# headstage.net
KiCad netlist of a schematic drawn in EAGLE
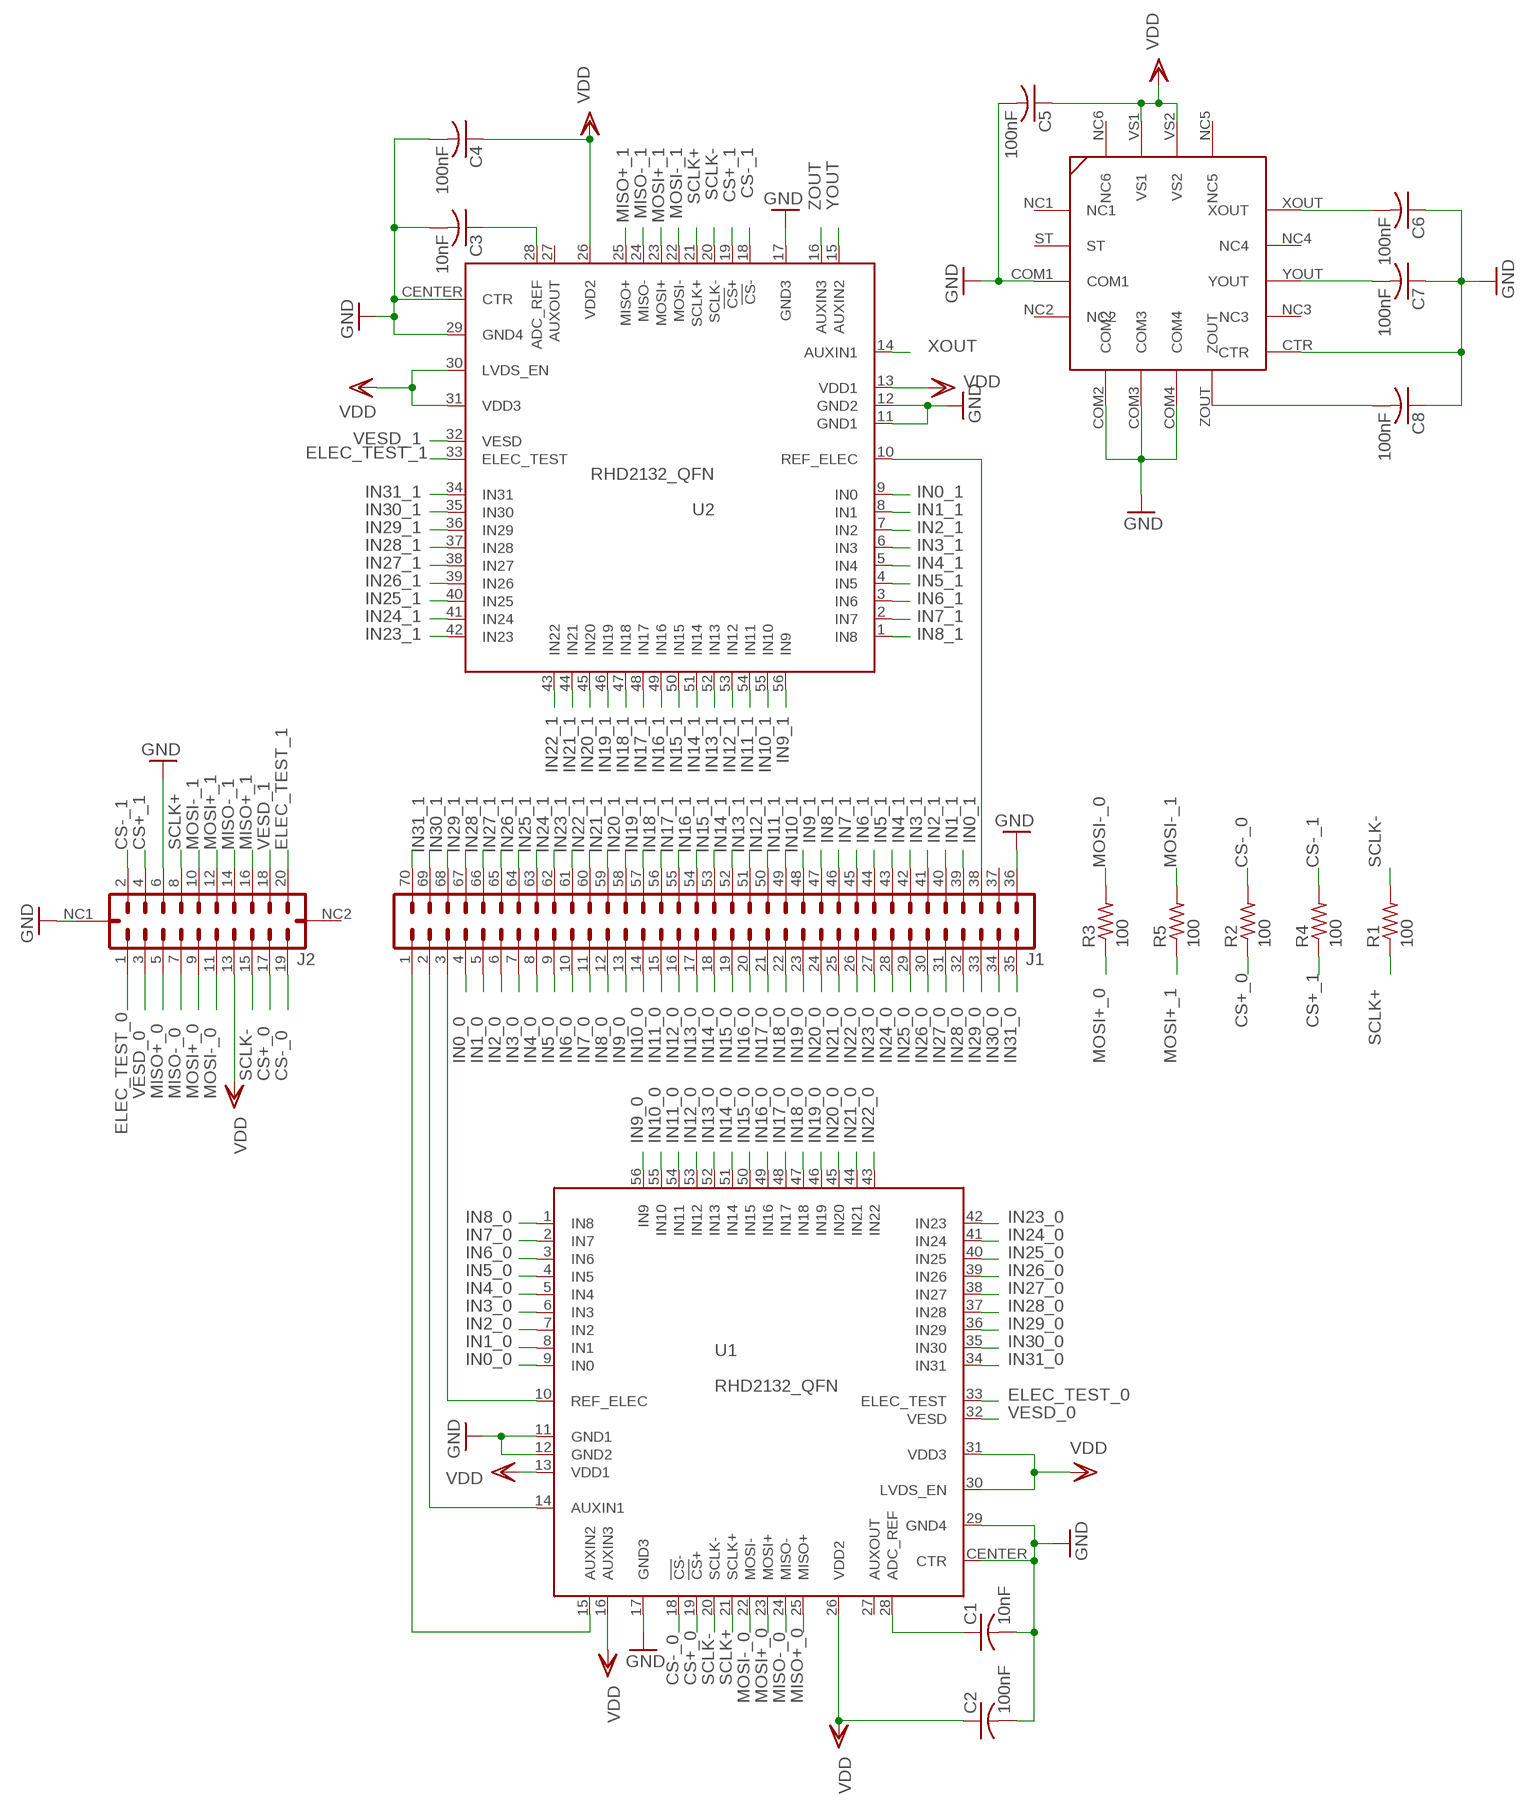
[diagram p0: schematic, sheet 1]

(export (version "E")
  (design (tool "Eeschema 10.0.6"))
  (components
    (comp (ref "C1")
      (value "10nF")
      (footprint "eagle-import:C0402K")
      (libsource (lib "eagle-import") (part "C-USC0402K"))
    )
    (comp (ref "C2")
      (value "100nF")
      (footprint "eagle-import:C0402K")
      (libsource (lib "eagle-import") (part "C-USC0402K"))
    )
    (comp (ref "C3")
      (value "10nF")
      (footprint "eagle-import:C0402K")
      (libsource (lib "eagle-import") (part "C-USC0402K"))
    )
    (comp (ref "C4")
      (value "100nF")
      (footprint "eagle-import:C0402K")
      (libsource (lib "eagle-import") (part "C-USC0402K"))
    )
    (comp (ref "C5")
      (value "100nF")
      (footprint "eagle-import:C0402K")
      (libsource (lib "eagle-import") (part "C-USC0402K"))
    )
    (comp (ref "C6")
      (value "100nF")
      (footprint "eagle-import:C0402K")
      (libsource (lib "eagle-import") (part "C-USC0402K"))
    )
    (comp (ref "C7")
      (value "100nF")
      (footprint "eagle-import:C0402K")
      (libsource (lib "eagle-import") (part "C-USC0402K"))
    )
    (comp (ref "C8")
      (value "100nF")
      (footprint "eagle-import:C0402K")
      (libsource (lib "eagle-import") (part "C-USC0402K"))
    )
    (comp (ref "J1")
      (value "HIROSE_DF40C-70DS-0.4V(51)")
      (footprint "eagle-import:HIROSE_DF40C-70DP")
      (libsource (lib "eagle-import") (part "HIROSE_DF40-70DP"))
    )
    (comp (ref "J2")
      (value "MOLEX_501190-2017")
      (footprint "eagle-import:MOLEX_501190-2017")
      (libsource (lib "eagle-import") (part "MOLEX_501190-2017"))
    )
    (comp (ref "R1")
      (value "100")
      (footprint "eagle-import:R0402")
      (libsource (lib "eagle-import") (part "R-US_R0402"))
    )
    (comp (ref "R2")
      (value "100")
      (footprint "eagle-import:R0402")
      (libsource (lib "eagle-import") (part "R-US_R0402"))
    )
    (comp (ref "R3")
      (value "100")
      (footprint "eagle-import:R0402")
      (libsource (lib "eagle-import") (part "R-US_R0402"))
    )
    (comp (ref "R4")
      (value "100")
      (footprint "eagle-import:R0402")
      (libsource (lib "eagle-import") (part "R-US_R0402"))
    )
    (comp (ref "R5")
      (value "100")
      (footprint "eagle-import:R0402")
      (libsource (lib "eagle-import") (part "R-US_R0402"))
    )
    (comp (ref "U1")
      (value "RHD2132_QFN")
      (footprint "eagle-import:QFN56_8_X_8_LARGE")
      (libsource (lib "eagle-import") (part "RHD2132_QFN"))
    )
    (comp (ref "U2")
      (value "RHD2132_QFN")
      (footprint "eagle-import:QFN56_8_X_8_LARGE")
      (libsource (lib "eagle-import") (part "RHD2132_QFN"))
    )
    (comp (ref "U3")
      (value "ADXL335")
      (footprint "eagle-import:ADXL335")
      (libsource (lib "eagle-import") (part "ADXL335"))
    )
  )
  (nets
    (net (code "1") (name "/CS+_0") (class "Default")
      (node (ref "J2") (pin "17") (pinfunction "17_17") (pintype "passive"))
      (node (ref "R2") (pin "1") (pinfunction "1_1") (pintype "passive"))
      (node (ref "U1") (pin "19") (pinfunction "~{CS}+_19") (pintype "input"))
    )
    (net (code "2") (name "/CS+_1") (class "Default")
      (node (ref "J2") (pin "4") (pinfunction "4_4") (pintype "passive"))
      (node (ref "R4") (pin "1") (pinfunction "1_1") (pintype "passive"))
      (node (ref "U2") (pin "19") (pinfunction "~{CS}+_19") (pintype "input"))
    )
    (net (code "3") (name "/CS-_0") (class "Default")
      (node (ref "J2") (pin "19") (pinfunction "19_19") (pintype "passive"))
      (node (ref "R2") (pin "2") (pinfunction "2_2") (pintype "passive"))
      (node (ref "U1") (pin "18") (pinfunction "~{CS}-_18") (pintype "input"))
    )
    (net (code "4") (name "/CS-_1") (class "Default")
      (node (ref "J2") (pin "2") (pinfunction "2_2") (pintype "passive"))
      (node (ref "R4") (pin "2") (pinfunction "2_2") (pintype "passive"))
      (node (ref "U2") (pin "18") (pinfunction "~{CS}-_18") (pintype "input"))
    )
    (net (code "5") (name "/ELEC_TEST_0") (class "Default")
      (node (ref "J2") (pin "1") (pinfunction "1_1") (pintype "passive"))
      (node (ref "U1") (pin "33") (pinfunction "ELEC_TEST_33") (pintype "input"))
    )
    (net (code "6") (name "/ELEC_TEST_1") (class "Default")
      (node (ref "J2") (pin "20") (pinfunction "20_20") (pintype "passive"))
      (node (ref "U2") (pin "33") (pinfunction "ELEC_TEST_33") (pintype "input"))
    )
    (net (code "7") (name "/IN0_0") (class "Default")
      (node (ref "J1") (pin "4") (pinfunction "4_4") (pintype "passive"))
      (node (ref "U1") (pin "9") (pinfunction "IN0_9") (pintype "input"))
    )
    (net (code "8") (name "/IN0_1") (class "Default")
      (node (ref "J1") (pin "39") (pinfunction "39_39") (pintype "passive"))
      (node (ref "U2") (pin "9") (pinfunction "IN0_9") (pintype "input"))
    )
    (net (code "9") (name "/IN1_0") (class "Default")
      (node (ref "J1") (pin "5") (pinfunction "5_5") (pintype "passive"))
      (node (ref "U1") (pin "8") (pinfunction "IN1_8") (pintype "input"))
    )
    (net (code "10") (name "/IN1_1") (class "Default")
      (node (ref "J1") (pin "40") (pinfunction "40_40") (pintype "passive"))
      (node (ref "U2") (pin "8") (pinfunction "IN1_8") (pintype "input"))
    )
    (net (code "11") (name "/IN2_0") (class "Default")
      (node (ref "J1") (pin "6") (pinfunction "6_6") (pintype "passive"))
      (node (ref "U1") (pin "7") (pinfunction "IN2_7") (pintype "input"))
    )
    (net (code "12") (name "/IN2_1") (class "Default")
      (node (ref "J1") (pin "41") (pinfunction "41_41") (pintype "passive"))
      (node (ref "U2") (pin "7") (pinfunction "IN2_7") (pintype "input"))
    )
    (net (code "13") (name "/IN3_0") (class "Default")
      (node (ref "J1") (pin "7") (pinfunction "7_7") (pintype "passive"))
      (node (ref "U1") (pin "6") (pinfunction "IN3_6") (pintype "input"))
    )
    (net (code "14") (name "/IN3_1") (class "Default")
      (node (ref "J1") (pin "42") (pinfunction "42_42") (pintype "passive"))
      (node (ref "U2") (pin "6") (pinfunction "IN3_6") (pintype "input"))
    )
    (net (code "15") (name "/IN4_0") (class "Default")
      (node (ref "J1") (pin "8") (pinfunction "8_8") (pintype "passive"))
      (node (ref "U1") (pin "5") (pinfunction "IN4_5") (pintype "input"))
    )
    (net (code "16") (name "/IN4_1") (class "Default")
      (node (ref "J1") (pin "43") (pinfunction "43_43") (pintype "passive"))
      (node (ref "U2") (pin "5") (pinfunction "IN4_5") (pintype "input"))
    )
    (net (code "17") (name "/IN5_0") (class "Default")
      (node (ref "J1") (pin "9") (pinfunction "9_9") (pintype "passive"))
      (node (ref "U1") (pin "4") (pinfunction "IN5_4") (pintype "input"))
    )
    (net (code "18") (name "/IN5_1") (class "Default")
      (node (ref "J1") (pin "44") (pinfunction "44_44") (pintype "passive"))
      (node (ref "U2") (pin "4") (pinfunction "IN5_4") (pintype "input"))
    )
    (net (code "19") (name "/IN6_0") (class "Default")
      (node (ref "J1") (pin "10") (pinfunction "10_10") (pintype "passive"))
      (node (ref "U1") (pin "3") (pinfunction "IN6_3") (pintype "input"))
    )
    (net (code "20") (name "/IN6_1") (class "Default")
      (node (ref "J1") (pin "45") (pinfunction "45_45") (pintype "passive"))
      (node (ref "U2") (pin "3") (pinfunction "IN6_3") (pintype "input"))
    )
    (net (code "21") (name "/IN7_0") (class "Default")
      (node (ref "J1") (pin "11") (pinfunction "11_11") (pintype "passive"))
      (node (ref "U1") (pin "2") (pinfunction "IN7_2") (pintype "input"))
    )
    (net (code "22") (name "/IN7_1") (class "Default")
      (node (ref "J1") (pin "46") (pinfunction "46_46") (pintype "passive"))
      (node (ref "U2") (pin "2") (pinfunction "IN7_2") (pintype "input"))
    )
    (net (code "23") (name "/IN8_0") (class "Default")
      (node (ref "J1") (pin "12") (pinfunction "12_12") (pintype "passive"))
      (node (ref "U1") (pin "1") (pinfunction "IN8_1") (pintype "input"))
    )
    (net (code "24") (name "/IN8_1") (class "Default")
      (node (ref "J1") (pin "47") (pinfunction "47_47") (pintype "passive"))
      (node (ref "U2") (pin "1") (pinfunction "IN8_1") (pintype "input"))
    )
    (net (code "25") (name "/IN9_0") (class "Default")
      (node (ref "J1") (pin "13") (pinfunction "13_13") (pintype "passive"))
      (node (ref "U1") (pin "56") (pinfunction "IN9_56") (pintype "input"))
    )
    (net (code "26") (name "/IN9_1") (class "Default")
      (node (ref "J1") (pin "48") (pinfunction "48_48") (pintype "passive"))
      (node (ref "U2") (pin "56") (pinfunction "IN9_56") (pintype "input"))
    )
    (net (code "27") (name "/IN10_0") (class "Default")
      (node (ref "J1") (pin "14") (pinfunction "14_14") (pintype "passive"))
      (node (ref "U1") (pin "55") (pinfunction "IN10_55") (pintype "input"))
    )
    (net (code "28") (name "/IN10_1") (class "Default")
      (node (ref "J1") (pin "49") (pinfunction "49_49") (pintype "passive"))
      (node (ref "U2") (pin "55") (pinfunction "IN10_55") (pintype "input"))
    )
    (net (code "29") (name "/IN11_0") (class "Default")
      (node (ref "J1") (pin "15") (pinfunction "15_15") (pintype "passive"))
      (node (ref "U1") (pin "54") (pinfunction "IN11_54") (pintype "input"))
    )
    (net (code "30") (name "/IN11_1") (class "Default")
      (node (ref "J1") (pin "50") (pinfunction "50_50") (pintype "passive"))
      (node (ref "U2") (pin "54") (pinfunction "IN11_54") (pintype "input"))
    )
    (net (code "31") (name "/IN12_0") (class "Default")
      (node (ref "J1") (pin "16") (pinfunction "16_16") (pintype "passive"))
      (node (ref "U1") (pin "53") (pinfunction "IN12_53") (pintype "input"))
    )
    (net (code "32") (name "/IN12_1") (class "Default")
      (node (ref "J1") (pin "51") (pinfunction "51_51") (pintype "passive"))
      (node (ref "U2") (pin "53") (pinfunction "IN12_53") (pintype "input"))
    )
    (net (code "33") (name "/IN13_0") (class "Default")
      (node (ref "J1") (pin "17") (pinfunction "17_17") (pintype "passive"))
      (node (ref "U1") (pin "52") (pinfunction "IN13_52") (pintype "input"))
    )
    (net (code "34") (name "/IN13_1") (class "Default")
      (node (ref "J1") (pin "52") (pinfunction "52_52") (pintype "passive"))
      (node (ref "U2") (pin "52") (pinfunction "IN13_52") (pintype "input"))
    )
    (net (code "35") (name "/IN14_0") (class "Default")
      (node (ref "J1") (pin "18") (pinfunction "18_18") (pintype "passive"))
      (node (ref "U1") (pin "51") (pinfunction "IN14_51") (pintype "input"))
    )
    (net (code "36") (name "/IN14_1") (class "Default")
      (node (ref "J1") (pin "53") (pinfunction "53_53") (pintype "passive"))
      (node (ref "U2") (pin "51") (pinfunction "IN14_51") (pintype "input"))
    )
    (net (code "37") (name "/IN15_0") (class "Default")
      (node (ref "J1") (pin "19") (pinfunction "19_19") (pintype "passive"))
      (node (ref "U1") (pin "50") (pinfunction "IN15_50") (pintype "input"))
    )
    (net (code "38") (name "/IN15_1") (class "Default")
      (node (ref "J1") (pin "54") (pinfunction "54_54") (pintype "passive"))
      (node (ref "U2") (pin "50") (pinfunction "IN15_50") (pintype "input"))
    )
    (net (code "39") (name "/IN16_0") (class "Default")
      (node (ref "J1") (pin "20") (pinfunction "20_20") (pintype "passive"))
      (node (ref "U1") (pin "49") (pinfunction "IN16_49") (pintype "input"))
    )
    (net (code "40") (name "/IN16_1") (class "Default")
      (node (ref "J1") (pin "55") (pinfunction "55_55") (pintype "passive"))
      (node (ref "U2") (pin "49") (pinfunction "IN16_49") (pintype "input"))
    )
    (net (code "41") (name "/IN17_0") (class "Default")
      (node (ref "J1") (pin "21") (pinfunction "21_21") (pintype "passive"))
      (node (ref "U1") (pin "48") (pinfunction "IN17_48") (pintype "input"))
    )
    (net (code "42") (name "/IN17_1") (class "Default")
      (node (ref "J1") (pin "56") (pinfunction "56_56") (pintype "passive"))
      (node (ref "U2") (pin "48") (pinfunction "IN17_48") (pintype "input"))
    )
    (net (code "43") (name "/IN18_0") (class "Default")
      (node (ref "J1") (pin "22") (pinfunction "22_22") (pintype "passive"))
      (node (ref "U1") (pin "47") (pinfunction "IN18_47") (pintype "input"))
    )
    (net (code "44") (name "/IN18_1") (class "Default")
      (node (ref "J1") (pin "57") (pinfunction "57_57") (pintype "passive"))
      (node (ref "U2") (pin "47") (pinfunction "IN18_47") (pintype "input"))
    )
    (net (code "45") (name "/IN19_0") (class "Default")
      (node (ref "J1") (pin "23") (pinfunction "23_23") (pintype "passive"))
      (node (ref "U1") (pin "46") (pinfunction "IN19_46") (pintype "input"))
    )
    (net (code "46") (name "/IN19_1") (class "Default")
      (node (ref "J1") (pin "58") (pinfunction "58_58") (pintype "passive"))
      (node (ref "U2") (pin "46") (pinfunction "IN19_46") (pintype "input"))
    )
    (net (code "47") (name "/IN20_0") (class "Default")
      (node (ref "J1") (pin "24") (pinfunction "24_24") (pintype "passive"))
      (node (ref "U1") (pin "45") (pinfunction "IN20_45") (pintype "input"))
    )
    (net (code "48") (name "/IN20_1") (class "Default")
      (node (ref "J1") (pin "59") (pinfunction "59_59") (pintype "passive"))
      (node (ref "U2") (pin "45") (pinfunction "IN20_45") (pintype "input"))
    )
    (net (code "49") (name "/IN21_0") (class "Default")
      (node (ref "J1") (pin "25") (pinfunction "25_25") (pintype "passive"))
      (node (ref "U1") (pin "44") (pinfunction "IN21_44") (pintype "input"))
    )
    (net (code "50") (name "/IN21_1") (class "Default")
      (node (ref "J1") (pin "60") (pinfunction "60_60") (pintype "passive"))
      (node (ref "U2") (pin "44") (pinfunction "IN21_44") (pintype "input"))
    )
    (net (code "51") (name "/IN22_0") (class "Default")
      (node (ref "J1") (pin "26") (pinfunction "26_26") (pintype "passive"))
      (node (ref "U1") (pin "43") (pinfunction "IN22_43") (pintype "input"))
    )
    (net (code "52") (name "/IN22_1") (class "Default")
      (node (ref "J1") (pin "61") (pinfunction "61_61") (pintype "passive"))
      (node (ref "U2") (pin "43") (pinfunction "IN22_43") (pintype "input"))
    )
    (net (code "53") (name "/IN23_0") (class "Default")
      (node (ref "J1") (pin "27") (pinfunction "27_27") (pintype "passive"))
      (node (ref "U1") (pin "42") (pinfunction "IN23_42") (pintype "input"))
    )
    (net (code "54") (name "/IN23_1") (class "Default")
      (node (ref "J1") (pin "62") (pinfunction "62_62") (pintype "passive"))
      (node (ref "U2") (pin "42") (pinfunction "IN23_42") (pintype "input"))
    )
    (net (code "55") (name "/IN24_0") (class "Default")
      (node (ref "J1") (pin "28") (pinfunction "28_28") (pintype "passive"))
      (node (ref "U1") (pin "41") (pinfunction "IN24_41") (pintype "input"))
    )
    (net (code "56") (name "/IN24_1") (class "Default")
      (node (ref "J1") (pin "63") (pinfunction "63_63") (pintype "passive"))
      (node (ref "U2") (pin "41") (pinfunction "IN24_41") (pintype "input"))
    )
    (net (code "57") (name "/IN25_0") (class "Default")
      (node (ref "J1") (pin "29") (pinfunction "29_29") (pintype "passive"))
      (node (ref "U1") (pin "40") (pinfunction "IN25_40") (pintype "input"))
    )
    (net (code "58") (name "/IN25_1") (class "Default")
      (node (ref "J1") (pin "64") (pinfunction "64_64") (pintype "passive"))
      (node (ref "U2") (pin "40") (pinfunction "IN25_40") (pintype "input"))
    )
    (net (code "59") (name "/IN26_0") (class "Default")
      (node (ref "J1") (pin "30") (pinfunction "30_30") (pintype "passive"))
      (node (ref "U1") (pin "39") (pinfunction "IN26_39") (pintype "input"))
    )
    (net (code "60") (name "/IN26_1") (class "Default")
      (node (ref "J1") (pin "65") (pinfunction "65_65") (pintype "passive"))
      (node (ref "U2") (pin "39") (pinfunction "IN26_39") (pintype "input"))
    )
    (net (code "61") (name "/IN27_0") (class "Default")
      (node (ref "J1") (pin "31") (pinfunction "31_31") (pintype "passive"))
      (node (ref "U1") (pin "38") (pinfunction "IN27_38") (pintype "input"))
    )
    (net (code "62") (name "/IN27_1") (class "Default")
      (node (ref "J1") (pin "66") (pinfunction "66_66") (pintype "passive"))
      (node (ref "U2") (pin "38") (pinfunction "IN27_38") (pintype "input"))
    )
    (net (code "63") (name "/IN28_0") (class "Default")
      (node (ref "J1") (pin "32") (pinfunction "32_32") (pintype "passive"))
      (node (ref "U1") (pin "37") (pinfunction "IN28_37") (pintype "input"))
    )
    (net (code "64") (name "/IN28_1") (class "Default")
      (node (ref "J1") (pin "67") (pinfunction "67_67") (pintype "passive"))
      (node (ref "U2") (pin "37") (pinfunction "IN28_37") (pintype "input"))
    )
    (net (code "65") (name "/IN29_0") (class "Default")
      (node (ref "J1") (pin "33") (pinfunction "33_33") (pintype "passive"))
      (node (ref "U1") (pin "36") (pinfunction "IN29_36") (pintype "input"))
    )
    (net (code "66") (name "/IN29_1") (class "Default")
      (node (ref "J1") (pin "68") (pinfunction "68_68") (pintype "passive"))
      (node (ref "U2") (pin "36") (pinfunction "IN29_36") (pintype "input"))
    )
    (net (code "67") (name "/IN30_0") (class "Default")
      (node (ref "J1") (pin "34") (pinfunction "34_34") (pintype "passive"))
      (node (ref "U1") (pin "35") (pinfunction "IN30_35") (pintype "input"))
    )
    (net (code "68") (name "/IN30_1") (class "Default")
      (node (ref "J1") (pin "69") (pinfunction "69_69") (pintype "passive"))
      (node (ref "U2") (pin "35") (pinfunction "IN30_35") (pintype "input"))
    )
    (net (code "69") (name "/IN31_0") (class "Default")
      (node (ref "J1") (pin "35") (pinfunction "35_35") (pintype "passive"))
      (node (ref "U1") (pin "34") (pinfunction "IN31_34") (pintype "input"))
    )
    (net (code "70") (name "/IN31_1") (class "Default")
      (node (ref "J1") (pin "70") (pinfunction "70_70") (pintype "passive"))
      (node (ref "U2") (pin "34") (pinfunction "IN31_34") (pintype "input"))
    )
    (net (code "71") (name "/MISO+_0") (class "Default")
      (node (ref "J2") (pin "5") (pinfunction "5_5") (pintype "passive"))
      (node (ref "U1") (pin "25") (pinfunction "MISO+_25") (pintype "output"))
    )
    (net (code "72") (name "/MISO+_1") (class "Default")
      (node (ref "J2") (pin "16") (pinfunction "16_16") (pintype "passive"))
      (node (ref "U2") (pin "25") (pinfunction "MISO+_25") (pintype "output"))
    )
    (net (code "73") (name "/MISO-_0") (class "Default")
      (node (ref "J2") (pin "7") (pinfunction "7_7") (pintype "passive"))
      (node (ref "U1") (pin "24") (pinfunction "MISO-_24") (pintype "output"))
    )
    (net (code "74") (name "/MISO-_1") (class "Default")
      (node (ref "J2") (pin "14") (pinfunction "14_14") (pintype "passive"))
      (node (ref "U2") (pin "24") (pinfunction "MISO-_24") (pintype "output"))
    )
    (net (code "75") (name "/MOSI+_0") (class "Default")
      (node (ref "J2") (pin "9") (pinfunction "9_9") (pintype "passive"))
      (node (ref "R3") (pin "1") (pinfunction "1_1") (pintype "passive"))
      (node (ref "U1") (pin "23") (pinfunction "MOSI+_23") (pintype "input"))
    )
    (net (code "76") (name "/MOSI+_1") (class "Default")
      (node (ref "J2") (pin "12") (pinfunction "12_12") (pintype "passive"))
      (node (ref "R5") (pin "1") (pinfunction "1_1") (pintype "passive"))
      (node (ref "U2") (pin "23") (pinfunction "MOSI+_23") (pintype "input"))
    )
    (net (code "77") (name "/MOSI-_0") (class "Default")
      (node (ref "J2") (pin "11") (pinfunction "11_11") (pintype "passive"))
      (node (ref "R3") (pin "2") (pinfunction "2_2") (pintype "passive"))
      (node (ref "U1") (pin "22") (pinfunction "MOSI-_22") (pintype "input"))
    )
    (net (code "78") (name "/MOSI-_1") (class "Default")
      (node (ref "J2") (pin "10") (pinfunction "10_10") (pintype "passive"))
      (node (ref "R5") (pin "2") (pinfunction "2_2") (pintype "passive"))
      (node (ref "U2") (pin "22") (pinfunction "MOSI-_22") (pintype "input"))
    )
    (net (code "79") (name "/SCLK+") (class "Default")
      (node (ref "J2") (pin "8") (pinfunction "8_8") (pintype "passive"))
      (node (ref "R1") (pin "1") (pinfunction "1_1") (pintype "passive"))
      (node (ref "U1") (pin "21") (pinfunction "SCLK+_21") (pintype "input"))
      (node (ref "U2") (pin "21") (pinfunction "SCLK+_21") (pintype "input"))
    )
    (net (code "80") (name "/SCLK-") (class "Default")
      (node (ref "J2") (pin "15") (pinfunction "15_15") (pintype "passive"))
      (node (ref "R1") (pin "2") (pinfunction "2_2") (pintype "passive"))
      (node (ref "U1") (pin "20") (pinfunction "SCLK-_20") (pintype "input"))
      (node (ref "U2") (pin "20") (pinfunction "SCLK-_20") (pintype "input"))
    )
    (net (code "81") (name "/VESD_0") (class "Default")
      (node (ref "J2") (pin "3") (pinfunction "3_3") (pintype "passive"))
      (node (ref "U1") (pin "32") (pinfunction "VESD_32") (pintype "power_in"))
    )
    (net (code "82") (name "/VESD_1") (class "Default")
      (node (ref "J2") (pin "18") (pinfunction "18_18") (pintype "passive"))
      (node (ref "U2") (pin "32") (pinfunction "VESD_32") (pintype "power_in"))
    )
    (net (code "83") (name "/XOUT") (class "Default")
      (node (ref "C6") (pin "2") (pinfunction "2_2") (pintype "passive"))
      (node (ref "U2") (pin "14") (pinfunction "AUXIN1_14") (pintype "input"))
      (node (ref "U3") (pin "XOUT") (pinfunction "XOUT_XOUT") (pintype "bidirectional"))
    )
    (net (code "84") (name "/YOUT") (class "Default")
      (node (ref "C7") (pin "2") (pinfunction "2_2") (pintype "passive"))
      (node (ref "U2") (pin "15") (pinfunction "AUXIN2_15") (pintype "input"))
      (node (ref "U3") (pin "YOUT") (pinfunction "YOUT_YOUT") (pintype "bidirectional"))
    )
    (net (code "85") (name "/ZOUT") (class "Default")
      (node (ref "C8") (pin "2") (pinfunction "2_2") (pintype "passive"))
      (node (ref "U2") (pin "16") (pinfunction "AUXIN3_16") (pintype "input"))
      (node (ref "U3") (pin "ZOUT") (pinfunction "ZOUT_ZOUT") (pintype "bidirectional"))
    )
    (net (code "86") (name "GND") (class "Default")
      (node (ref "C1") (pin "2") (pinfunction "2_2") (pintype "passive"))
      (node (ref "C2") (pin "2") (pinfunction "2_2") (pintype "passive"))
      (node (ref "C3") (pin "2") (pinfunction "2_2") (pintype "passive"))
      (node (ref "C4") (pin "2") (pinfunction "2_2") (pintype "passive"))
      (node (ref "C5") (pin "2") (pinfunction "2_2") (pintype "passive"))
      (node (ref "C6") (pin "1") (pinfunction "1_1") (pintype "passive"))
      (node (ref "C7") (pin "1") (pinfunction "1_1") (pintype "passive"))
      (node (ref "C8") (pin "1") (pinfunction "1_1") (pintype "passive"))
      (node (ref "J1") (pin "36") (pinfunction "36_36") (pintype "passive"))
      (node (ref "J2") (pin "6") (pinfunction "6_6") (pintype "passive"))
      (node (ref "J2") (pin "NC1") (pinfunction "NC1_NC1") (pintype "passive"))
      (node (ref "U1") (pin "11") (pinfunction "GND1_11") (pintype "power_in"))
      (node (ref "U1") (pin "12") (pinfunction "GND2_12") (pintype "power_in"))
      (node (ref "U1") (pin "17") (pinfunction "GND3_17") (pintype "power_in"))
      (node (ref "U1") (pin "29") (pinfunction "GND4_29") (pintype "power_in"))
      (node (ref "U1") (pin "CENTER") (pinfunction "CTR_CENTER") (pintype "power_in"))
      (node (ref "U2") (pin "11") (pinfunction "GND1_11") (pintype "power_in"))
      (node (ref "U2") (pin "12") (pinfunction "GND2_12") (pintype "power_in"))
      (node (ref "U2") (pin "17") (pinfunction "GND3_17") (pintype "power_in"))
      (node (ref "U2") (pin "29") (pinfunction "GND4_29") (pintype "power_in"))
      (node (ref "U2") (pin "CENTER") (pinfunction "CTR_CENTER") (pintype "power_in"))
      (node (ref "U3") (pin "COM1") (pinfunction "COM1_COM1") (pintype "bidirectional"))
      (node (ref "U3") (pin "COM2") (pinfunction "COM2_COM2") (pintype "bidirectional"))
      (node (ref "U3") (pin "COM3") (pinfunction "COM3_COM3") (pintype "bidirectional"))
      (node (ref "U3") (pin "COM4") (pinfunction "COM4_COM4") (pintype "bidirectional"))
      (node (ref "U3") (pin "CTR") (pinfunction "CTR_CTR") (pintype "bidirectional"))
    )
    (net (code "87") (name "Net-(U1-ADC_REF)") (class "Default")
      (node (ref "C1") (pin "1") (pinfunction "1_1") (pintype "passive"))
      (node (ref "U1") (pin "28") (pinfunction "ADC_REF_28") (pintype "passive"))
    )
    (net (code "88") (name "Net-(U1-AUXIN1)") (class "Default")
      (node (ref "J1") (pin "2") (pinfunction "2_2") (pintype "passive"))
      (node (ref "U1") (pin "14") (pinfunction "AUXIN1_14") (pintype "input"))
    )
    (net (code "89") (name "Net-(U1-AUXIN2)") (class "Default")
      (node (ref "J1") (pin "1") (pinfunction "1_1") (pintype "passive"))
      (node (ref "U1") (pin "15") (pinfunction "AUXIN2_15") (pintype "input"))
    )
    (net (code "90") (name "Net-(U1-REF_ELEC)") (class "Default")
      (node (ref "J1") (pin "3") (pinfunction "3_3") (pintype "passive"))
      (node (ref "U1") (pin "10") (pinfunction "REF_ELEC_10") (pintype "input"))
    )
    (net (code "91") (name "Net-(U2-ADC_REF)") (class "Default")
      (node (ref "C3") (pin "1") (pinfunction "1_1") (pintype "passive"))
      (node (ref "U2") (pin "28") (pinfunction "ADC_REF_28") (pintype "passive"))
    )
    (net (code "92") (name "Net-(U2-REF_ELEC)") (class "Default")
      (node (ref "J1") (pin "38") (pinfunction "38_38") (pintype "passive"))
      (node (ref "U2") (pin "10") (pinfunction "REF_ELEC_10") (pintype "input"))
    )
    (net (code "93") (name "VDD") (class "Default")
      (node (ref "C2") (pin "1") (pinfunction "1_1") (pintype "passive"))
      (node (ref "C4") (pin "1") (pinfunction "1_1") (pintype "passive"))
      (node (ref "C5") (pin "1") (pinfunction "1_1") (pintype "passive"))
      (node (ref "J2") (pin "13") (pinfunction "13_13") (pintype "passive"))
      (node (ref "U1") (pin "13") (pinfunction "VDD1_13") (pintype "power_in"))
      (node (ref "U1") (pin "16") (pinfunction "AUXIN3_16") (pintype "input"))
      (node (ref "U1") (pin "26") (pinfunction "VDD2_26") (pintype "power_in"))
      (node (ref "U1") (pin "30") (pinfunction "LVDS_EN_30") (pintype "input"))
      (node (ref "U1") (pin "31") (pinfunction "VDD3_31") (pintype "power_in"))
      (node (ref "U2") (pin "13") (pinfunction "VDD1_13") (pintype "power_in"))
      (node (ref "U2") (pin "26") (pinfunction "VDD2_26") (pintype "power_in"))
      (node (ref "U2") (pin "30") (pinfunction "LVDS_EN_30") (pintype "input"))
      (node (ref "U2") (pin "31") (pinfunction "VDD3_31") (pintype "power_in"))
      (node (ref "U3") (pin "VS1") (pinfunction "VS1_VS1") (pintype "bidirectional"))
      (node (ref "U3") (pin "VS2") (pinfunction "VS2_VS2") (pintype "bidirectional"))
    )
    (net (code "94") (name "unconnected-(J1-Pad37)") (class "Default")
      (node (ref "J1") (pin "37") (pinfunction "37_37") (pintype "passive"))
    )
    (net (code "95") (name "unconnected-(J2-PadNC2)") (class "Default")
      (node (ref "J2") (pin "NC2") (pinfunction "NC2_NC2") (pintype "passive"))
    )
    (net (code "96") (name "unconnected-(U1-AUXOUT-Pad27)") (class "Default")
      (node (ref "U1") (pin "27") (pinfunction "AUXOUT_27") (pintype "tri_state"))
    )
    (net (code "97") (name "unconnected-(U2-AUXOUT-Pad27)") (class "Default")
      (node (ref "U2") (pin "27") (pinfunction "AUXOUT_27") (pintype "tri_state"))
    )
    (net (code "98") (name "unconnected-(U3-PadNC1)") (class "Default")
      (node (ref "U3") (pin "NC1") (pinfunction "NC1_NC1") (pintype "bidirectional"))
    )
    (net (code "99") (name "unconnected-(U3-PadNC2)") (class "Default")
      (node (ref "U3") (pin "NC2") (pinfunction "NC2_NC2") (pintype "bidirectional"))
    )
    (net (code "100") (name "unconnected-(U3-PadNC3)") (class "Default")
      (node (ref "U3") (pin "NC3") (pinfunction "NC3_NC3") (pintype "bidirectional"))
    )
    (net (code "101") (name "unconnected-(U3-PadNC4)") (class "Default")
      (node (ref "U3") (pin "NC4") (pinfunction "NC4_NC4") (pintype "bidirectional"))
    )
    (net (code "102") (name "unconnected-(U3-PadNC5)") (class "Default")
      (node (ref "U3") (pin "NC5") (pinfunction "NC5_NC5") (pintype "bidirectional"))
    )
    (net (code "103") (name "unconnected-(U3-PadNC6)") (class "Default")
      (node (ref "U3") (pin "NC6") (pinfunction "NC6_NC6") (pintype "bidirectional"))
    )
    (net (code "104") (name "unconnected-(U3-PadST)") (class "Default")
      (node (ref "U3") (pin "ST") (pinfunction "ST_ST") (pintype "bidirectional"))
    )
  )
)
